# object01.net
KiCad netlist of a schematic drawn in EAGLE
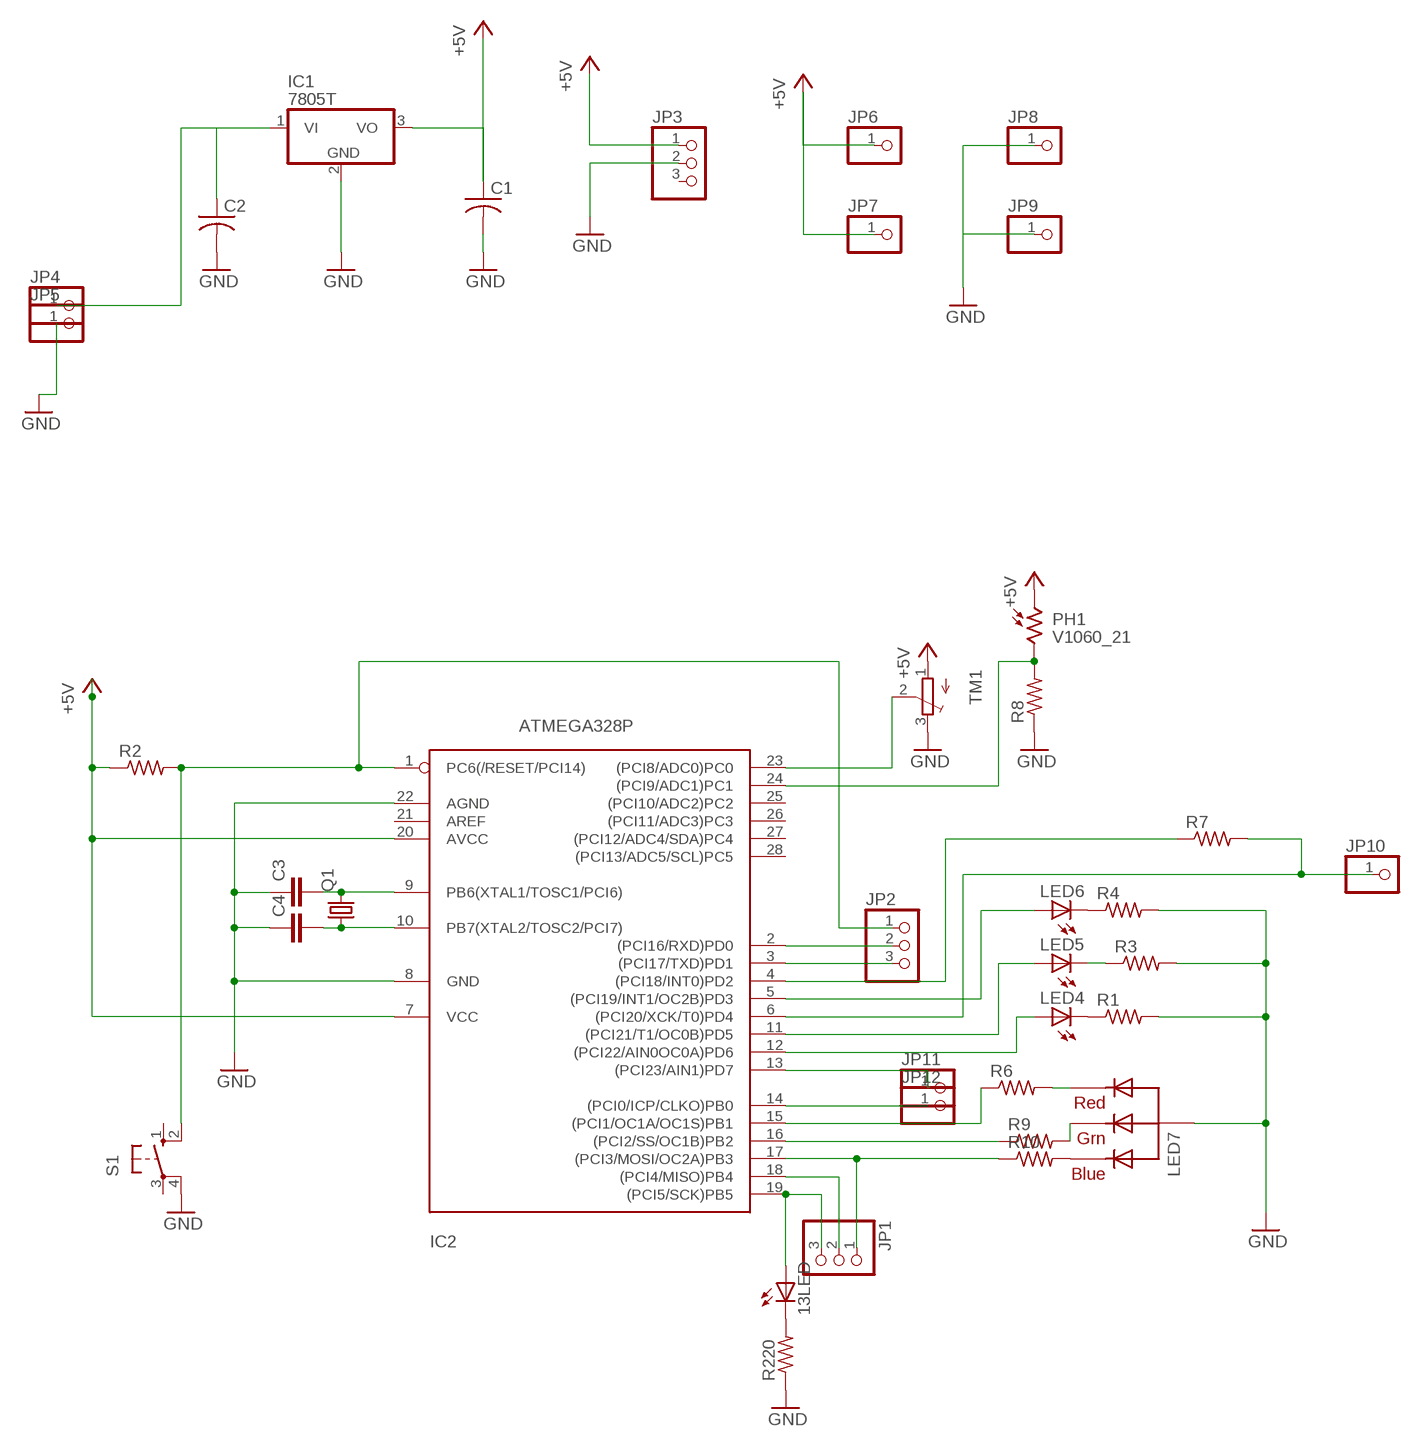
[diagram p0: schematic, sheet 1]

(export (version "E")
  (design (tool "Eeschema 10.0.6"))
  (components
    (comp (ref "13LED")
      (value "LED5MM")
      (footprint "eagle-import:LED5MM")
      (libsource (lib "eagle-import") (part "LED5MM"))
    )
    (comp (ref "C1")
      (value "C-US050-024X044")
      (footprint "eagle-import:C050-024X044")
      (libsource (lib "eagle-import") (part "C-US050-024X044"))
    )
    (comp (ref "C2")
      (value "C-US050-024X044")
      (footprint "eagle-import:C050-024X044")
      (libsource (lib "eagle-import") (part "C-US050-024X044"))
    )
    (comp (ref "C3")
      (value "C-EU025-024X044")
      (footprint "eagle-import:C025-024X044")
      (libsource (lib "eagle-import") (part "C-EU025-024X044"))
    )
    (comp (ref "C4")
      (value "C-EU025-024X044")
      (footprint "eagle-import:C025-024X044")
      (libsource (lib "eagle-import") (part "C-EU025-024X044"))
    )
    (comp (ref "IC1")
      (value "7805T")
      (footprint "eagle-import:TO220H")
      (libsource (lib "eagle-import") (part "78T05"))
    )
    (comp (ref "IC2")
      (value "ATMEGA328P")
      (footprint "eagle-import:DIL28-3")
      (libsource (lib "eagle-import") (part "ATMEGA328P"))
    )
    (comp (ref "JP1")
      (value "PINHD-1X3CB")
      (footprint "eagle-import:1X03-CLEANBIG")
      (libsource (lib "eagle-import") (part "PINHD-1X3CB"))
    )
    (comp (ref "JP2")
      (value "PINHD-1X3CB")
      (footprint "eagle-import:1X03-CLEANBIG")
      (libsource (lib "eagle-import") (part "PINHD-1X3CB"))
    )
    (comp (ref "JP3")
      (value "PINHD-1X3CB")
      (footprint "eagle-import:1X03-CLEANBIG")
      (libsource (lib "eagle-import") (part "PINHD-1X3CB"))
    )
    (comp (ref "JP4")
      (value "PINHD-1X1")
      (footprint "eagle-import:1X01")
      (libsource (lib "eagle-import") (part "PINHD-1X1"))
    )
    (comp (ref "JP5")
      (value "PINHD-1X1")
      (footprint "eagle-import:1X01")
      (libsource (lib "eagle-import") (part "PINHD-1X1"))
    )
    (comp (ref "JP6")
      (value "PINHD-1X1")
      (footprint "eagle-import:1X01")
      (libsource (lib "eagle-import") (part "PINHD-1X1"))
    )
    (comp (ref "JP7")
      (value "PINHD-1X1")
      (footprint "eagle-import:1X01")
      (libsource (lib "eagle-import") (part "PINHD-1X1"))
    )
    (comp (ref "JP8")
      (value "PINHD-1X1")
      (footprint "eagle-import:1X01")
      (libsource (lib "eagle-import") (part "PINHD-1X1"))
    )
    (comp (ref "JP9")
      (value "PINHD-1X1")
      (footprint "eagle-import:1X01")
      (libsource (lib "eagle-import") (part "PINHD-1X1"))
    )
    (comp (ref "JP10")
      (value "PINHD-1X1")
      (footprint "eagle-import:1X01")
      (libsource (lib "eagle-import") (part "PINHD-1X1"))
    )
    (comp (ref "JP11")
      (value "PINHD-1X1")
      (footprint "eagle-import:1X01")
      (libsource (lib "eagle-import") (part "PINHD-1X1"))
    )
    (comp (ref "JP12")
      (value "PINHD-1X1")
      (footprint "eagle-import:1X01")
      (libsource (lib "eagle-import") (part "PINHD-1X1"))
    )
    (comp (ref "LED4")
      (value "LED5MM")
      (footprint "eagle-import:LED5MM")
      (libsource (lib "eagle-import") (part "LED5MM"))
    )
    (comp (ref "LED5")
      (value "LED5MM")
      (footprint "eagle-import:LED5MM")
      (libsource (lib "eagle-import") (part "LED5MM"))
    )
    (comp (ref "LED6")
      (value "LED5MM")
      (footprint "eagle-import:LED5MM")
      (libsource (lib "eagle-import") (part "LED5MM"))
    )
    (comp (ref "LED7")
      (value "RGBLED_CA-5MM")
      (footprint "eagle-import:LED5MMRGB")
      (libsource (lib "eagle-import") (part "RGBLED_CA-5MM"))
    )
    (comp (ref "PH1")
      (value "V1060_21")
      (footprint "eagle-import:TO-5_V10")
      (libsource (lib "eagle-import") (part "?1060V_21"))
    )
    (comp (ref "Q1")
      (value "CRYSTALHC49U-V")
      (footprint "eagle-import:HC49U-V")
      (libsource (lib "eagle-import") (part "CRYSTALHC49U-V"))
    )
    (comp (ref "R1")
      (value "R-US_0207/10")
      (footprint "eagle-import:0207_10")
      (libsource (lib "eagle-import") (part "R-US_0207/10"))
    )
    (comp (ref "R2")
      (value "R-US_0204/5")
      (footprint "eagle-import:0204_5")
      (libsource (lib "eagle-import") (part "R-US_0204/5"))
    )
    (comp (ref "R3")
      (value "R-US_0207/10")
      (footprint "eagle-import:0207_10")
      (libsource (lib "eagle-import") (part "R-US_0207/10"))
    )
    (comp (ref "R4")
      (value "R-US_0207/10")
      (footprint "eagle-import:0207_10")
      (libsource (lib "eagle-import") (part "R-US_0207/10"))
    )
    (comp (ref "R6")
      (value "R-US_0207/10")
      (footprint "eagle-import:0207_10")
      (libsource (lib "eagle-import") (part "R-US_0207/10"))
    )
    (comp (ref "R7")
      (value "R-US_0207/10")
      (footprint "eagle-import:0207_10")
      (libsource (lib "eagle-import") (part "R-US_0207/10"))
    )
    (comp (ref "R8")
      (value "R-US_0207/10")
      (footprint "eagle-import:0207_10")
      (libsource (lib "eagle-import") (part "R-US_0207/10"))
    )
    (comp (ref "R9")
      (value "R-US_0207/10")
      (footprint "eagle-import:0207_10")
      (libsource (lib "eagle-import") (part "R-US_0207/10"))
    )
    (comp (ref "R10")
      (value "R-US_0207/10")
      (footprint "eagle-import:0207_10")
      (libsource (lib "eagle-import") (part "R-US_0207/10"))
    )
    (comp (ref "R220")
      (value "R-US_0207/10")
      (footprint "eagle-import:0207_10")
      (libsource (lib "eagle-import") (part "R-US_0207/10"))
    )
    (comp (ref "S1")
      (value "10-XX")
      (footprint "eagle-import:B3F-10XX")
      (fields (field (name "MPN") "B3F-1000"))
      (libsource (lib "eagle-import") (part "10-XX"))
    )
    (comp (ref "TM1")
      (value "TRIMPOT3386")
      (footprint "eagle-import:TRIM-3386")
      (libsource (lib "eagle-import") (part "TRIMPOT3386"))
    )
  )
  (nets
    (net (code "1") (name "+5V") (class "Default")
      (node (ref "C1") (pin "1") (pinfunction "1_1") (pintype "passive"))
      (node (ref "IC1") (pin "3") (pinfunction "VO_3") (pintype "passive"))
      (node (ref "IC2") (pin "20") (pinfunction "AVCC_20") (pintype "bidirectional"))
      (node (ref "IC2") (pin "7") (pinfunction "VCC_7") (pintype "bidirectional"))
      (node (ref "JP3") (pin "1") (pinfunction "1_1") (pintype "passive"))
      (node (ref "JP6") (pin "1") (pinfunction "1_1") (pintype "passive"))
      (node (ref "JP7") (pin "1") (pinfunction "1_1") (pintype "passive"))
      (node (ref "PH1") (pin "1") (pinfunction "1_1") (pintype "passive"))
      (node (ref "R2") (pin "1") (pinfunction "1_1") (pintype "passive"))
      (node (ref "TM1") (pin "1") (pinfunction "A_1") (pintype "passive"))
    )
    (net (code "2") (name "GND") (class "Default")
      (node (ref "C1") (pin "2") (pinfunction "2_2") (pintype "passive"))
      (node (ref "C2") (pin "2") (pinfunction "2_2") (pintype "passive"))
      (node (ref "C3") (pin "1") (pinfunction "1_1") (pintype "passive"))
      (node (ref "C4") (pin "1") (pinfunction "1_1") (pintype "passive"))
      (node (ref "IC1") (pin "2") (pinfunction "GND_2") (pintype "passive"))
      (node (ref "IC2") (pin "22") (pinfunction "AGND_22") (pintype "bidirectional"))
      (node (ref "IC2") (pin "8") (pinfunction "GND_8") (pintype "bidirectional"))
      (node (ref "JP3") (pin "2") (pinfunction "2_2") (pintype "passive"))
      (node (ref "JP5") (pin "1") (pinfunction "1_1") (pintype "passive"))
      (node (ref "JP8") (pin "1") (pinfunction "1_1") (pintype "passive"))
      (node (ref "JP9") (pin "1") (pinfunction "1_1") (pintype "passive"))
      (node (ref "LED7") (pin "2") (pinfunction "VCC_2") (pintype "bidirectional"))
      (node (ref "R1") (pin "2") (pinfunction "2_2") (pintype "passive"))
      (node (ref "R220") (pin "1") (pinfunction "1_1") (pintype "passive"))
      (node (ref "R3") (pin "2") (pinfunction "2_2") (pintype "passive"))
      (node (ref "R4") (pin "2") (pinfunction "2_2") (pintype "passive"))
      (node (ref "R8") (pin "1") (pinfunction "1_1") (pintype "passive"))
      (node (ref "S1") (pin "4") (pinfunction "P1_4") (pintype "passive"))
      (node (ref "TM1") (pin "3") (pinfunction "E_3") (pintype "passive"))
    )
    (net (code "3") (name "Net-(13LED-C)") (class "Default")
      (node (ref "13LED") (pin "K") (pinfunction "C_K") (pintype "passive"))
      (node (ref "R220") (pin "2") (pinfunction "2_2") (pintype "passive"))
    )
    (net (code "4") (name "Net-(IC1-VI)") (class "Default")
      (node (ref "C2") (pin "1") (pinfunction "1_1") (pintype "passive"))
      (node (ref "IC1") (pin "1") (pinfunction "VI_1") (pintype "input"))
      (node (ref "JP4") (pin "1") (pinfunction "1_1") (pintype "passive"))
    )
    (net (code "5") (name "Net-(IC2-(PCI0{slash}ICP{slash}CLKO)PB0)") (class "Default")
      (node (ref "IC2") (pin "14") (pinfunction "(PCI0/ICP/CLKO)PB0_14") (pintype "bidirectional"))
      (node (ref "JP12") (pin "1") (pinfunction "1_1") (pintype "passive"))
    )
    (net (code "6") (name "Net-(IC2-(PCI1{slash}OC1A{slash}OC1S)PB1)") (class "Default")
      (node (ref "IC2") (pin "15") (pinfunction "(PCI1/OC1A/OC1S)PB1_15") (pintype "bidirectional"))
      (node (ref "R6") (pin "1") (pinfunction "1_1") (pintype "passive"))
    )
    (net (code "7") (name "Net-(IC2-(PCI2{slash}SS{slash}OC1B)PB2)") (class "Default")
      (node (ref "IC2") (pin "16") (pinfunction "(PCI2/SS/OC1B)PB2_16") (pintype "bidirectional"))
      (node (ref "R9") (pin "1") (pinfunction "1_1") (pintype "passive"))
    )
    (net (code "8") (name "Net-(IC2-(PCI3{slash}MOSI{slash}OC2A)PB3)") (class "Default")
      (node (ref "IC2") (pin "17") (pinfunction "(PCI3/MOSI/OC2A)PB3_17") (pintype "bidirectional"))
      (node (ref "JP1") (pin "1") (pinfunction "1_1") (pintype "passive"))
      (node (ref "R10") (pin "1") (pinfunction "1_1") (pintype "passive"))
    )
    (net (code "9") (name "Net-(IC2-(PCI4{slash}MISO)PB4)") (class "Default")
      (node (ref "IC2") (pin "18") (pinfunction "(PCI4/MISO)PB4_18") (pintype "bidirectional"))
      (node (ref "JP1") (pin "2") (pinfunction "2_2") (pintype "passive"))
    )
    (net (code "10") (name "Net-(IC2-(PCI5{slash}SCK)PB5)") (class "Default")
      (node (ref "13LED") (pin "A") (pinfunction "A_A") (pintype "passive"))
      (node (ref "IC2") (pin "19") (pinfunction "(PCI5/SCK)PB5_19") (pintype "bidirectional"))
      (node (ref "JP1") (pin "3") (pinfunction "3_3") (pintype "passive"))
    )
    (net (code "11") (name "Net-(IC2-(PCI8{slash}ADC0)PC0)") (class "Default")
      (node (ref "IC2") (pin "23") (pinfunction "(PCI8/ADC0)PC0_23") (pintype "bidirectional"))
      (node (ref "TM1") (pin "2") (pinfunction "S_2") (pintype "passive"))
    )
    (net (code "12") (name "Net-(IC2-(PCI9{slash}ADC1)PC1)") (class "Default")
      (node (ref "IC2") (pin "24") (pinfunction "(PCI9/ADC1)PC1_24") (pintype "bidirectional"))
      (node (ref "PH1") (pin "2") (pinfunction "2_2") (pintype "passive"))
      (node (ref "R8") (pin "2") (pinfunction "2_2") (pintype "passive"))
    )
    (net (code "13") (name "Net-(IC2-(PCI16{slash}RXD)PD0)") (class "Default")
      (node (ref "IC2") (pin "2") (pinfunction "(PCI16/RXD)PD0_2") (pintype "bidirectional"))
      (node (ref "JP2") (pin "2") (pinfunction "2_2") (pintype "passive"))
    )
    (net (code "14") (name "Net-(IC2-(PCI17{slash}TXD)PD1)") (class "Default")
      (node (ref "IC2") (pin "3") (pinfunction "(PCI17/TXD)PD1_3") (pintype "bidirectional"))
      (node (ref "JP2") (pin "3") (pinfunction "3_3") (pintype "passive"))
    )
    (net (code "15") (name "Net-(IC2-(PCI18{slash}INT0)PD2)") (class "Default")
      (node (ref "IC2") (pin "4") (pinfunction "(PCI18/INT0)PD2_4") (pintype "bidirectional"))
      (node (ref "R7") (pin "1") (pinfunction "1_1") (pintype "passive"))
    )
    (net (code "16") (name "Net-(IC2-(PCI19{slash}INT1{slash}OC2B)PD3)") (class "Default")
      (node (ref "IC2") (pin "5") (pinfunction "(PCI19/INT1/OC2B)PD3_5") (pintype "bidirectional"))
      (node (ref "LED6") (pin "A") (pinfunction "A_A") (pintype "passive"))
    )
    (net (code "17") (name "Net-(IC2-(PCI20{slash}XCK{slash}T0)PD4)") (class "Default")
      (node (ref "IC2") (pin "6") (pinfunction "(PCI20/XCK/T0)PD4_6") (pintype "bidirectional"))
      (node (ref "JP10") (pin "1") (pinfunction "1_1") (pintype "passive"))
      (node (ref "R7") (pin "2") (pinfunction "2_2") (pintype "passive"))
    )
    (net (code "18") (name "Net-(IC2-(PCI21{slash}T1{slash}OC0B)PD5)") (class "Default")
      (node (ref "IC2") (pin "11") (pinfunction "(PCI21/T1/OC0B)PD5_11") (pintype "bidirectional"))
      (node (ref "LED5") (pin "A") (pinfunction "A_A") (pintype "passive"))
    )
    (net (code "19") (name "Net-(IC2-(PCI22{slash}AIN0OC0A)PD6)") (class "Default")
      (node (ref "IC2") (pin "12") (pinfunction "(PCI22/AIN0OC0A)PD6_12") (pintype "bidirectional"))
      (node (ref "LED4") (pin "A") (pinfunction "A_A") (pintype "passive"))
    )
    (net (code "20") (name "Net-(IC2-(PCI23{slash}AIN1)PD7)") (class "Default")
      (node (ref "IC2") (pin "13") (pinfunction "(PCI23/AIN1)PD7_13") (pintype "bidirectional"))
      (node (ref "JP11") (pin "1") (pinfunction "1_1") (pintype "passive"))
    )
    (net (code "21") (name "Net-(IC2-PB6(XTAL1{slash}TOSC1{slash}PCI6))") (class "Default")
      (node (ref "C3") (pin "2") (pinfunction "2_2") (pintype "passive"))
      (node (ref "IC2") (pin "9") (pinfunction "PB6(XTAL1/TOSC1/PCI6)_9") (pintype "bidirectional"))
      (node (ref "Q1") (pin "2") (pinfunction "2_2") (pintype "passive"))
    )
    (net (code "22") (name "Net-(IC2-PB7(XTAL2{slash}TOSC2{slash}PCI7))") (class "Default")
      (node (ref "C4") (pin "2") (pinfunction "2_2") (pintype "passive"))
      (node (ref "IC2") (pin "10") (pinfunction "PB7(XTAL2/TOSC2/PCI7)_10") (pintype "bidirectional"))
      (node (ref "Q1") (pin "1") (pinfunction "1_1") (pintype "passive"))
    )
    (net (code "23") (name "Net-(IC2-PC6({slash}RESET{slash}PCI14))") (class "Default")
      (node (ref "IC2") (pin "1") (pinfunction "PC6(/RESET/PCI14)_1") (pintype "bidirectional"))
      (node (ref "JP2") (pin "1") (pinfunction "1_1") (pintype "passive"))
      (node (ref "R2") (pin "2") (pinfunction "2_2") (pintype "passive"))
      (node (ref "S1") (pin "2") (pinfunction "S1_2") (pintype "passive"))
    )
    (net (code "24") (name "Net-(LED4-C)") (class "Default")
      (node (ref "LED4") (pin "K") (pinfunction "C_K") (pintype "passive"))
      (node (ref "R1") (pin "1") (pinfunction "1_1") (pintype "passive"))
    )
    (net (code "25") (name "Net-(LED5-C)") (class "Default")
      (node (ref "LED5") (pin "K") (pinfunction "C_K") (pintype "passive"))
      (node (ref "R3") (pin "1") (pinfunction "1_1") (pintype "passive"))
    )
    (net (code "26") (name "Net-(LED6-C)") (class "Default")
      (node (ref "LED6") (pin "K") (pinfunction "C_K") (pintype "passive"))
      (node (ref "R4") (pin "1") (pinfunction "1_1") (pintype "passive"))
    )
    (net (code "27") (name "Net-(LED7-BLUE)") (class "Default")
      (node (ref "LED7") (pin "4") (pinfunction "BLUE_4") (pintype "bidirectional"))
      (node (ref "R10") (pin "2") (pinfunction "2_2") (pintype "passive"))
    )
    (net (code "28") (name "Net-(LED7-GREEN)") (class "Default")
      (node (ref "LED7") (pin "3") (pinfunction "GREEN_3") (pintype "bidirectional"))
      (node (ref "R9") (pin "2") (pinfunction "2_2") (pintype "passive"))
    )
    (net (code "29") (name "Net-(LED7-RED)") (class "Default")
      (node (ref "LED7") (pin "1") (pinfunction "RED_1") (pintype "bidirectional"))
      (node (ref "R6") (pin "2") (pinfunction "2_2") (pintype "passive"))
    )
    (net (code "30") (name "unconnected-(IC2-(PCI10{slash}ADC2)PC2-Pad25)") (class "Default")
      (node (ref "IC2") (pin "25") (pinfunction "(PCI10/ADC2)PC2_25") (pintype "bidirectional"))
    )
    (net (code "31") (name "unconnected-(IC2-(PCI11{slash}ADC3)PC3-Pad26)") (class "Default")
      (node (ref "IC2") (pin "26") (pinfunction "(PCI11/ADC3)PC3_26") (pintype "bidirectional"))
    )
    (net (code "32") (name "unconnected-(IC2-(PCI12{slash}ADC4{slash}SDA)PC4-Pad27)") (class "Default")
      (node (ref "IC2") (pin "27") (pinfunction "(PCI12/ADC4/SDA)PC4_27") (pintype "bidirectional"))
    )
    (net (code "33") (name "unconnected-(IC2-(PCI13{slash}ADC5{slash}SCL)PC5-Pad28)") (class "Default")
      (node (ref "IC2") (pin "28") (pinfunction "(PCI13/ADC5/SCL)PC5_28") (pintype "bidirectional"))
    )
    (net (code "34") (name "unconnected-(IC2-AREF-Pad21)") (class "Default")
      (node (ref "IC2") (pin "21") (pinfunction "AREF_21") (pintype "bidirectional"))
    )
    (net (code "35") (name "unconnected-(JP3-Pad3)") (class "Default")
      (node (ref "JP3") (pin "3") (pinfunction "3_3") (pintype "passive"))
    )
    (net (code "36") (name "unconnected-(S1-P-Pad3)") (class "Default")
      (node (ref "S1") (pin "3") (pinfunction "P_3") (pintype "passive"))
    )
    (net (code "37") (name "unconnected-(S1-S-Pad1)") (class "Default")
      (node (ref "S1") (pin "1") (pinfunction "S_1") (pintype "passive"))
    )
  )
)
